# Power.net
KiCad netlist of a schematic drawn in Altium Designer
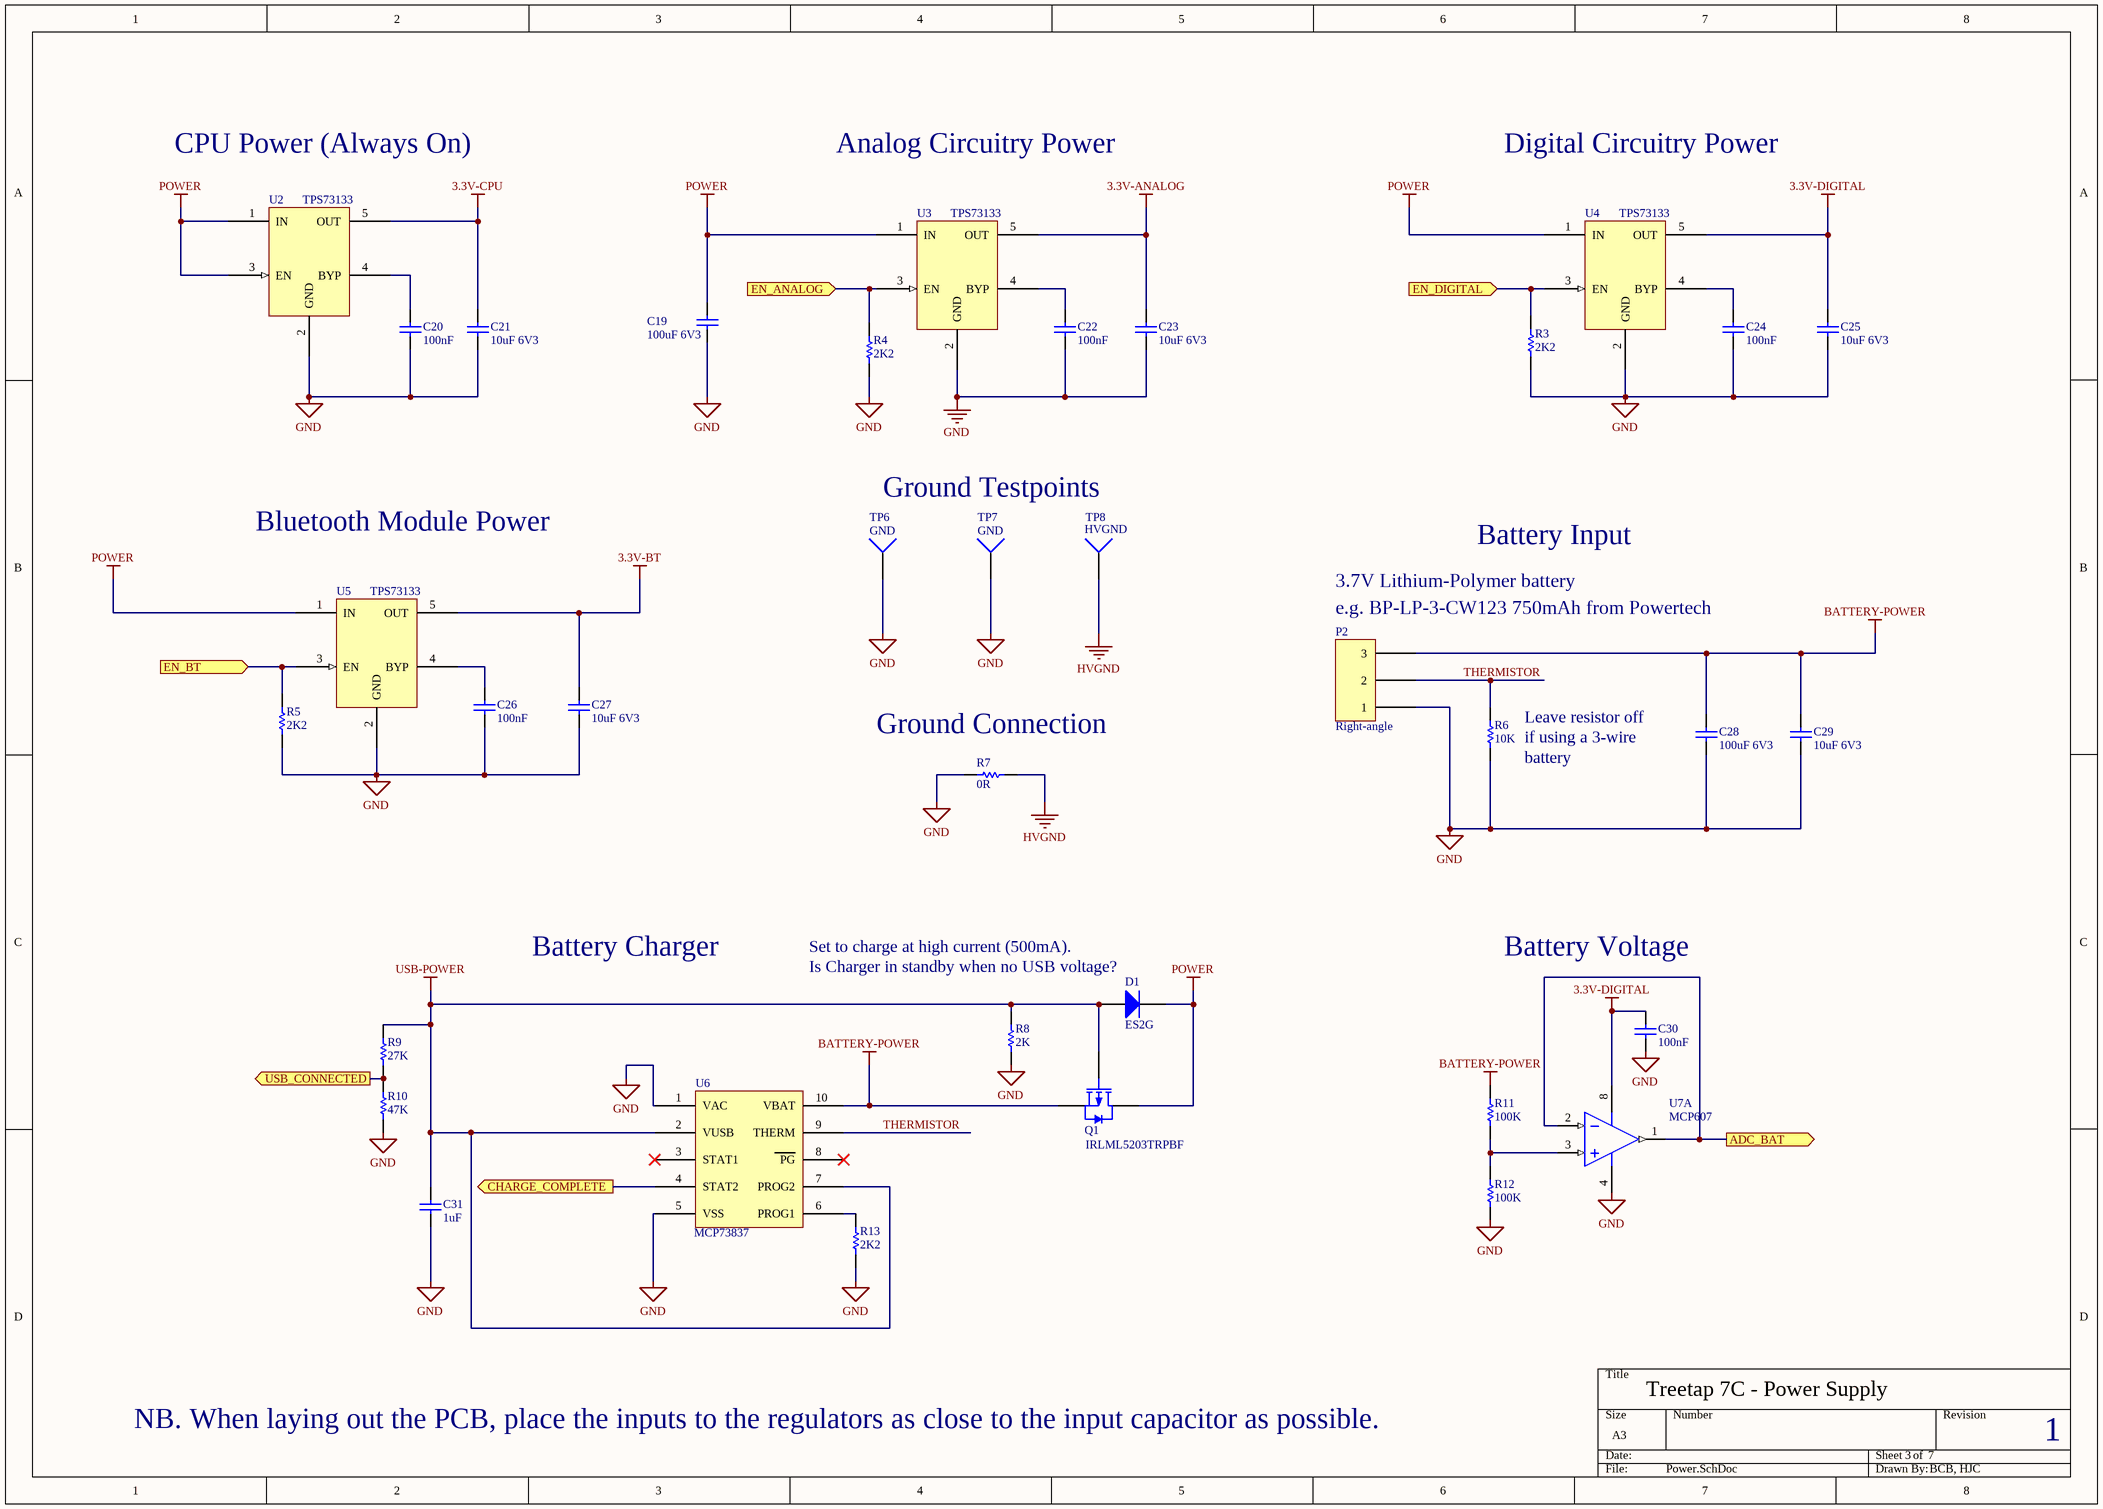
[diagram p0: Power.SchDoc]

(export (version "E")
  (design (tool "Eeschema 10.0.6"))
  (components
    (comp (ref "C19")
      (value "100uF 6V3")
      (footprint "CC1206")
      (description "100uF 6.3V 1206 multi-layer ceramic capacitor")
      (fields (field (name "PART NUMBER") "C1206C107M9PACTU") (field (name "MANUFACTURER") "Kemet"))
      (libsource (lib "TreetapParts") (part "100uF_1206_6V3"))
    )
    (comp (ref "C20")
      (value "100nF")
      (footprint "CC0603")
      (description "0603 Capacitor")
      (fields (field (name "PART NUMBER") "100nF_CC0603"))
      (libsource (lib "ECE_Component_Library_2") (part "100nF_CC0603"))
    )
    (comp (ref "C21")
      (value "10uF 6V3")
      (footprint "CC0603")
      (description "10uF 6.3V 0603 ceramic capacitor")
      (fields (field (name "MANUFACTURER") "Multicomp") (field (name "PART NUMBER") "MCCA000517"))
      (libsource (lib "TreetapParts") (part "10uF_CC0603_6V3"))
    )
    (comp (ref "C22")
      (value "100nF")
      (footprint "CC0603")
      (description "0603 Capacitor")
      (fields (field (name "PART NUMBER") "100nF_CC0603"))
      (libsource (lib "ECE_Component_Library_2") (part "100nF_CC0603"))
    )
    (comp (ref "C23")
      (value "10uF 6V3")
      (footprint "CC0603")
      (description "10uF 6.3V 0603 ceramic capacitor")
      (fields (field (name "MANUFACTURER") "Multicomp") (field (name "PART NUMBER") "MCCA000517"))
      (libsource (lib "TreetapParts") (part "10uF_CC0603_6V3"))
    )
    (comp (ref "C24")
      (value "100nF")
      (footprint "CC0603")
      (description "0603 Capacitor")
      (fields (field (name "PART NUMBER") "100nF_CC0603"))
      (libsource (lib "ECE_Component_Library_2") (part "100nF_CC0603"))
    )
    (comp (ref "C25")
      (value "10uF 6V3")
      (footprint "CC0603")
      (description "10uF 6.3V 0603 ceramic capacitor")
      (fields (field (name "MANUFACTURER") "Multicomp") (field (name "PART NUMBER") "MCCA000517"))
      (libsource (lib "TreetapParts") (part "10uF_CC0603_6V3"))
    )
    (comp (ref "C26")
      (value "100nF")
      (footprint "CC0603")
      (description "0603 Capacitor")
      (fields (field (name "PART NUMBER") "100nF_CC0603"))
      (libsource (lib "ECE_Component_Library_2") (part "100nF_CC0603"))
    )
    (comp (ref "C27")
      (value "10uF 6V3")
      (footprint "CC0603")
      (description "10uF 6.3V 0603 ceramic capacitor")
      (fields (field (name "MANUFACTURER") "Multicomp") (field (name "PART NUMBER") "MCCA000517"))
      (libsource (lib "TreetapParts") (part "10uF_CC0603_6V3"))
    )
    (comp (ref "C28")
      (value "100uF 6V3")
      (footprint "CC1206")
      (description "100uF 6.3V 1206 multi-layer ceramic capacitor")
      (fields (field (name "PART NUMBER") "C1206C107M9PACTU") (field (name "MANUFACTURER") "Kemet"))
      (libsource (lib "TreetapParts") (part "100uF_1206_6V3"))
    )
    (comp (ref "C29")
      (value "10uF 6V3")
      (footprint "CC0603")
      (description "10uF 6.3V 0603 ceramic capacitor")
      (fields (field (name "MANUFACTURER") "Multicomp") (field (name "PART NUMBER") "MCCA000517"))
      (libsource (lib "TreetapParts") (part "10uF_CC0603_6V3"))
    )
    (comp (ref "C30")
      (value "100nF")
      (footprint "CC0603")
      (description "0603 Capacitor")
      (fields (field (name "PART NUMBER") "100nF_CC0603"))
      (libsource (lib "ECE_Component_Library_2") (part "100nF_CC0603"))
    )
    (comp (ref "C31")
      (value "1uF")
      (footprint "CC0603")
      (description "1uF 25V 0603 ceramic capacitor")
      (fields (field (name "MANUFACTURER") "Kemet") (field (name "PART NUMBER") "C0603C105K3PAC"))
      (libsource (lib "TreetapParts") (part "1uF_0603_25V_ceramic"))
    )
    (comp (ref "D1")
      (value "ES2G")
      (footprint "DO214AA (SMB)")
      (description "Fast 2A 400V SMB diode, Vishay Semiconductor")
      (fields (field (name "MANUFACTURER") "Vishay General Semiconductor"))
      (libsource (lib "TreetapParts") (part "ES2G"))
    )
    (comp (ref "P2")
      (value "Right-angle")
      (footprint "3pinheader")
      (description "3 pin 2.54mm pitch right-angle header")
      (fields (field (name "MANUFACTURER") "(Multi-sourced part)"))
      (libsource (lib "TreetapParts") (part "3pinheader"))
    )
    (comp (ref "Q1")
      (value "IRLML5203TRPBF")
      (footprint "SOT-23")
      (description "30V P-channel enhancement mode MOSFET")
      (fields
        (field (name "MANUFACTURER") "International Rectifier")
        (field (name "PART NUMBER") "IRLML5203PBF")
      )
      (libsource (lib "TreetapParts") (part "IRLML5203TRPBF"))
    )
    (comp (ref "R3")
      (value "2K2")
      (footprint "R0603")
      (description "0603 Resistor")
      (fields (field (name "PART NUMBER") "2K2_R0603"))
      (libsource (lib "ECE_Component_Library_2") (part "2K2_R0603"))
    )
    (comp (ref "R4")
      (value "2K2")
      (footprint "R0603")
      (description "0603 Resistor")
      (fields (field (name "PART NUMBER") "2K2_R0603"))
      (libsource (lib "ECE_Component_Library_2") (part "2K2_R0603"))
    )
    (comp (ref "R5")
      (value "2K2")
      (footprint "R0603")
      (description "0603 Resistor")
      (fields (field (name "PART NUMBER") "2K2_R0603"))
      (libsource (lib "ECE_Component_Library_2") (part "2K2_R0603"))
    )
    (comp (ref "R6")
      (value "10K")
      (footprint "R0603")
      (description "0603 Resistor")
      (fields (field (name "PART NUMBER") "10K_R0603"))
      (libsource (lib "ECE_Component_Library_2") (part "10K_R0603"))
    )
    (comp (ref "R7")
      (value "0R")
      (footprint "R0603")
      (description "0603 Resistor")
      (fields (field (name "PART NUMBER") "0R_R0603"))
      (libsource (lib "ECE_Component_Library_2") (part "0R_R0603"))
    )
    (comp (ref "R8")
      (value "2K")
      (footprint "R0603")
      (description "0603 Resistor")
      (fields (field (name "PART NUMBER") "2K_R0603"))
      (libsource (lib "ECE_Component_Library_2") (part "2K_R0603"))
    )
    (comp (ref "R9")
      (value "27K")
      (footprint "R0603")
      (description "0603 Resistor")
      (fields (field (name "PART NUMBER") "27K_R0603"))
      (libsource (lib "ECE_Component_Library_2") (part "27K_R0603"))
    )
    (comp (ref "R10")
      (value "47K")
      (footprint "R0603")
      (description "0603 Resistor")
      (fields (field (name "PART NUMBER") "47K_R0603"))
      (libsource (lib "ECE_Component_Library_2") (part "47K_R0603"))
    )
    (comp (ref "R11")
      (value "100K")
      (footprint "R0603")
      (description "0603 Resistor")
      (fields (field (name "PART NUMBER") "100K_R0603"))
      (libsource (lib "ECE_Component_Library_2") (part "100K_R0603"))
    )
    (comp (ref "R12")
      (value "100K")
      (footprint "R0603")
      (description "0603 Resistor")
      (fields (field (name "PART NUMBER") "100K_R0603"))
      (libsource (lib "ECE_Component_Library_2") (part "100K_R0603"))
    )
    (comp (ref "R13")
      (value "2K2")
      (footprint "R0603")
      (description "0603 Resistor")
      (fields (field (name "PART NUMBER") "2K2_R0603"))
      (libsource (lib "ECE_Component_Library_2") (part "2K2_R0603"))
    )
    (comp (ref "TP6")
      (value "GND")
      (footprint "SMTP_1")
      (description "Test point hook (surface mount)")
      (fields (field (name "MANUFACTURER") "Harwin") (field (name "PART NUMBER") "S1751-46"))
      (libsource (lib "TreetapParts") (part "SMTestPoint"))
    )
    (comp (ref "TP7")
      (value "GND")
      (footprint "ThroughHoleTP")
      (description "Through hole testpoint - intended for a loop of wire.")
      (libsource (lib "TreetapParts") (part "ThroughHoleTP"))
    )
    (comp (ref "TP8")
      (value "HVGND")
      (footprint "SMTP_1")
      (description "Test point hook (surface mount)")
      (fields (field (name "MANUFACTURER") "Harwin") (field (name "PART NUMBER") "S1751-46"))
      (libsource (lib "TreetapParts") (part "SMTestPoint"))
    )
    (comp (ref "U2")
      (value "TPS73133")
      (footprint "DBV005")
      (description "150mA 3.3V linear regulator with 30mV dropout")
      (fields (field (name "MANUFACTURER") "Texas Instruments") (field (name "PART NUMBER") "TPS73133DBVTG4"))
      (libsource (lib "TreetapParts") (part "TPS73133"))
    )
    (comp (ref "U3")
      (value "TPS73133")
      (footprint "DBV005")
      (description "150mA 3.3V linear regulator with 30mV dropout")
      (fields (field (name "MANUFACTURER") "Texas Instruments") (field (name "PART NUMBER") "TPS73133DBVTG4"))
      (libsource (lib "TreetapParts") (part "TPS73133"))
    )
    (comp (ref "U4")
      (value "TPS73133")
      (footprint "DBV005")
      (description "150mA 3.3V linear regulator with 30mV dropout")
      (fields (field (name "MANUFACTURER") "Texas Instruments") (field (name "PART NUMBER") "TPS73133DBVTG4"))
      (libsource (lib "TreetapParts") (part "TPS73133"))
    )
    (comp (ref "U5")
      (value "TPS73133")
      (footprint "DBV005")
      (description "150mA 3.3V linear regulator with 30mV dropout")
      (fields (field (name "MANUFACTURER") "Texas Instruments") (field (name "PART NUMBER") "TPS73133DBVTG4"))
      (libsource (lib "TreetapParts") (part "TPS73133"))
    )
    (comp (ref "U6")
      (value "MCP73837")
      (footprint "10-MSOP")
      (description "USB Lithium Battery Charger")
      (fields (field (name "MANUFACTURER") "Microchip") (field (name "PART NUMBER") "MCP73837-FCI/UN"))
      (libsource (lib "TreetapParts") (part "MCP73837"))
    )
    (comp (ref "U7")
      (value "MCP607")
      (footprint "MS-012")
      (description "Dual micropower CMOS opamp")
      (fields (field (name "MANUFACTURER") "Microchip") (field (name "PART NUMBER") "MCP607-I/SN"))
      (libsource (lib "TreetapParts") (part "MCP607"))
    )
  )
  (nets
    (net (code "1") (name "/ADC_BAT") (class "Default")
      (node (ref "U7") (pin "1") (pinfunction "OUT_1") (pintype "output"))
      (node (ref "U7") (pin "2") (pinfunction "IN-_2") (pintype "input"))
    )
    (net (code "2") (name "/CHARGE_COMPLETE") (class "Default")
      (node (ref "U6") (pin "4") (pinfunction "STAT2_4") (pintype "passive"))
    )
    (net (code "3") (name "/EN_ANALOG") (class "Default")
      (node (ref "R4") (pin "2") (pinfunction "2_2") (pintype "passive"))
      (node (ref "U3") (pin "3") (pinfunction "EN_3") (pintype "input"))
    )
    (net (code "4") (name "/EN_BT") (class "Default")
      (node (ref "R5") (pin "2") (pinfunction "2_2") (pintype "passive"))
      (node (ref "U5") (pin "3") (pinfunction "EN_3") (pintype "input"))
    )
    (net (code "5") (name "/EN_DIGITAL") (class "Default")
      (node (ref "R3") (pin "2") (pinfunction "2_2") (pintype "passive"))
      (node (ref "U4") (pin "3") (pinfunction "EN_3") (pintype "input"))
    )
    (net (code "6") (name "/THERMISTOR") (class "Default")
      (node (ref "P2") (pin "2") (pinfunction "2_2") (pintype "passive"))
      (node (ref "R6") (pin "2") (pinfunction "2_2") (pintype "passive"))
      (node (ref "U6") (pin "9") (pinfunction "THERM_9") (pintype "passive"))
    )
    (net (code "7") (name "/USB_CONNECTED") (class "Default")
      (node (ref "R10") (pin "2") (pinfunction "2_2") (pintype "passive"))
      (node (ref "R9") (pin "1") (pinfunction "1_1") (pintype "passive"))
    )
    (net (code "8") (name "3.3V-ANALOG") (class "Default")
      (node (ref "C23") (pin "2") (pinfunction "2_2") (pintype "passive"))
      (node (ref "U3") (pin "5") (pinfunction "OUT_5") (pintype "power_in"))
    )
    (net (code "9") (name "3.3V-BT") (class "Default")
      (node (ref "C27") (pin "2") (pinfunction "2_2") (pintype "passive"))
      (node (ref "U5") (pin "5") (pinfunction "OUT_5") (pintype "power_in"))
    )
    (net (code "10") (name "3.3V-CPU") (class "Default")
      (node (ref "C21") (pin "2") (pinfunction "2_2") (pintype "passive"))
      (node (ref "U2") (pin "5") (pinfunction "OUT_5") (pintype "power_in"))
    )
    (net (code "11") (name "3.3V-DIGITAL") (class "Default")
      (node (ref "C25") (pin "2") (pinfunction "2_2") (pintype "passive"))
      (node (ref "C30") (pin "2") (pinfunction "2_2") (pintype "passive"))
      (node (ref "U4") (pin "5") (pinfunction "OUT_5") (pintype "power_in"))
      (node (ref "U7") (pin "8") (pinfunction "V+_8") (pintype "power_in"))
    )
    (net (code "12") (name "BATTERY-POWER") (class "Default")
      (node (ref "C28") (pin "1") (pinfunction "1_1") (pintype "passive"))
      (node (ref "C29") (pin "2") (pinfunction "2_2") (pintype "passive"))
      (node (ref "P2") (pin "3") (pinfunction "3_3") (pintype "passive"))
      (node (ref "Q1") (pin "3") (pinfunction "D_3") (pintype "passive"))
      (node (ref "R11") (pin "2") (pinfunction "2_2") (pintype "passive"))
      (node (ref "U6") (pin "10") (pinfunction "VBAT_10") (pintype "passive"))
    )
    (net (code "13") (name "GND") (class "Default")
      (node (ref "C19") (pin "1") (pinfunction "1_1") (pintype "passive"))
      (node (ref "C20") (pin "2") (pinfunction "2_2") (pintype "passive"))
      (node (ref "C21") (pin "1") (pinfunction "1_1") (pintype "passive"))
      (node (ref "C22") (pin "2") (pinfunction "2_2") (pintype "passive"))
      (node (ref "C23") (pin "1") (pinfunction "1_1") (pintype "passive"))
      (node (ref "C24") (pin "2") (pinfunction "2_2") (pintype "passive"))
      (node (ref "C25") (pin "1") (pinfunction "1_1") (pintype "passive"))
      (node (ref "C26") (pin "2") (pinfunction "2_2") (pintype "passive"))
      (node (ref "C27") (pin "1") (pinfunction "1_1") (pintype "passive"))
      (node (ref "C28") (pin "2") (pinfunction "2_2") (pintype "passive"))
      (node (ref "C29") (pin "1") (pinfunction "1_1") (pintype "passive"))
      (node (ref "C30") (pin "1") (pinfunction "1_1") (pintype "passive"))
      (node (ref "C31") (pin "1") (pinfunction "1_1") (pintype "passive"))
      (node (ref "P2") (pin "1") (pinfunction "1_1") (pintype "passive"))
      (node (ref "R10") (pin "1") (pinfunction "1_1") (pintype "passive"))
      (node (ref "R12") (pin "1") (pinfunction "1_1") (pintype "passive"))
      (node (ref "R13") (pin "1") (pinfunction "1_1") (pintype "passive"))
      (node (ref "R3") (pin "1") (pinfunction "1_1") (pintype "passive"))
      (node (ref "R4") (pin "1") (pinfunction "1_1") (pintype "passive"))
      (node (ref "R5") (pin "1") (pinfunction "1_1") (pintype "passive"))
      (node (ref "R6") (pin "1") (pinfunction "1_1") (pintype "passive"))
      (node (ref "R7") (pin "1") (pinfunction "1_1") (pintype "passive"))
      (node (ref "R8") (pin "1") (pinfunction "1_1") (pintype "passive"))
      (node (ref "TP6") (pin "1") (pinfunction "1_1") (pintype "passive"))
      (node (ref "TP7") (pin "1") (pinfunction "1_1") (pintype "passive"))
      (node (ref "U2") (pin "2") (pinfunction "GND_2") (pintype "power_in"))
      (node (ref "U3") (pin "2") (pinfunction "GND_2") (pintype "power_in"))
      (node (ref "U4") (pin "2") (pinfunction "GND_2") (pintype "power_in"))
      (node (ref "U5") (pin "2") (pinfunction "GND_2") (pintype "power_in"))
      (node (ref "U6") (pin "1") (pinfunction "VAC_1") (pintype "passive"))
      (node (ref "U6") (pin "5") (pinfunction "VSS_5") (pintype "passive"))
      (node (ref "U7") (pin "4") (pinfunction "GND_4") (pintype "power_in"))
    )
    (net (code "14") (name "HVGND") (class "Default")
      (node (ref "R7") (pin "2") (pinfunction "2_2") (pintype "passive"))
      (node (ref "TP8") (pin "1") (pinfunction "1_1") (pintype "passive"))
    )
    (net (code "15") (name "Net-(U2-BYP)") (class "Default")
      (node (ref "C20") (pin "1") (pinfunction "1_1") (pintype "passive"))
      (node (ref "U2") (pin "4") (pinfunction "BYP_4") (pintype "passive"))
    )
    (net (code "16") (name "Net-(U3-BYP)") (class "Default")
      (node (ref "C22") (pin "1") (pinfunction "1_1") (pintype "passive"))
      (node (ref "U3") (pin "4") (pinfunction "BYP_4") (pintype "passive"))
    )
    (net (code "17") (name "Net-(U4-BYP)") (class "Default")
      (node (ref "C24") (pin "1") (pinfunction "1_1") (pintype "passive"))
      (node (ref "U4") (pin "4") (pinfunction "BYP_4") (pintype "passive"))
    )
    (net (code "18") (name "Net-(U5-BYP)") (class "Default")
      (node (ref "C26") (pin "1") (pinfunction "1_1") (pintype "passive"))
      (node (ref "U5") (pin "4") (pinfunction "BYP_4") (pintype "passive"))
    )
    (net (code "19") (name "Net-(U6-PROG1)") (class "Default")
      (node (ref "R13") (pin "2") (pinfunction "2_2") (pintype "passive"))
      (node (ref "U6") (pin "6") (pinfunction "PROG1_6") (pintype "passive"))
    )
    (net (code "20") (name "Net-(U7A-IN+)") (class "Default")
      (node (ref "R11") (pin "1") (pinfunction "1_1") (pintype "passive"))
      (node (ref "R12") (pin "2") (pinfunction "2_2") (pintype "passive"))
      (node (ref "U7") (pin "3") (pinfunction "IN+_3") (pintype "input"))
    )
    (net (code "21") (name "POWER") (class "Default")
      (node (ref "C19") (pin "2") (pinfunction "2_2") (pintype "passive"))
      (node (ref "D1") (pin "2") (pinfunction "K_2") (pintype "passive"))
      (node (ref "Q1") (pin "2") (pinfunction "S_2") (pintype "passive"))
      (node (ref "U2") (pin "1") (pinfunction "IN_1") (pintype "power_in"))
      (node (ref "U2") (pin "3") (pinfunction "EN_3") (pintype "input"))
      (node (ref "U3") (pin "1") (pinfunction "IN_1") (pintype "power_in"))
      (node (ref "U4") (pin "1") (pinfunction "IN_1") (pintype "power_in"))
      (node (ref "U5") (pin "1") (pinfunction "IN_1") (pintype "power_in"))
    )
    (net (code "22") (name "USB-POWER") (class "Default")
      (node (ref "C31") (pin "2") (pinfunction "2_2") (pintype "passive"))
      (node (ref "D1") (pin "1") (pinfunction "A_1") (pintype "passive"))
      (node (ref "Q1") (pin "1") (pinfunction "G_1") (pintype "passive"))
      (node (ref "R8") (pin "2") (pinfunction "2_2") (pintype "passive"))
      (node (ref "R9") (pin "2") (pinfunction "2_2") (pintype "passive"))
      (node (ref "U6") (pin "2") (pinfunction "VUSB_2") (pintype "passive"))
      (node (ref "U6") (pin "7") (pinfunction "PROG2_7") (pintype "passive"))
    )
    (net (code "23") (name "unconnected-(U6-PG-Pad8)") (class "Default")
      (node (ref "U6") (pin "8") (pinfunction "PG_8") (pintype "passive+no_connect"))
    )
    (net (code "24") (name "unconnected-(U6-STAT1-Pad3)") (class "Default")
      (node (ref "U6") (pin "3") (pinfunction "STAT1_3") (pintype "passive+no_connect"))
    )
  )
)
